# raspiledmeter.net
KiCad netlist of a schematic drawn in EAGLE
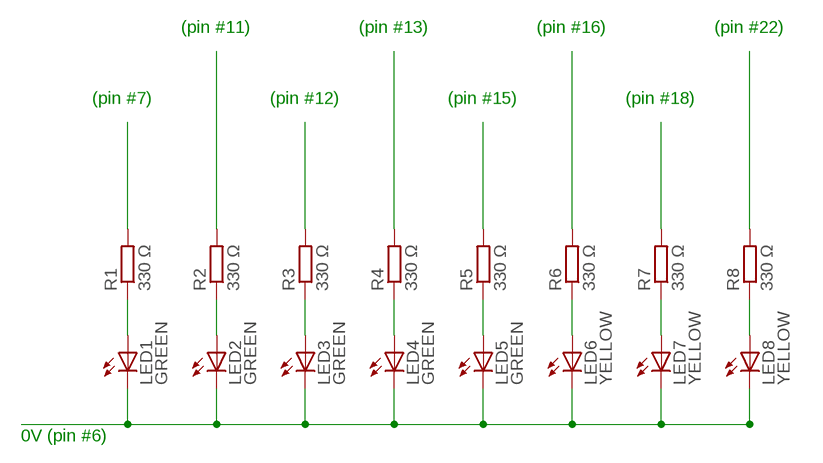
[diagram p0: schematic, sheet 1]

(export (version "E")
  (design (tool "Eeschema 10.0.6"))
  (components
    (comp (ref "LED1")
      (value "GREEN")
      (footprint "eagle-import:PLCC2")
      (libsource (lib "eagle-import") (part "_T679-?-1E1F1LG"))
    )
    (comp (ref "LED2")
      (value "GREEN")
      (footprint "eagle-import:PLCC2")
      (libsource (lib "eagle-import") (part "_T679-?-1E1F1LG"))
    )
    (comp (ref "LED3")
      (value "GREEN")
      (footprint "eagle-import:PLCC2")
      (libsource (lib "eagle-import") (part "_T679-?-1E1F1LG"))
    )
    (comp (ref "LED4")
      (value "GREEN")
      (footprint "eagle-import:PLCC2")
      (libsource (lib "eagle-import") (part "_T679-?-1E1F1LG"))
    )
    (comp (ref "LED5")
      (value "GREEN")
      (footprint "eagle-import:PLCC2")
      (libsource (lib "eagle-import") (part "_T679-?-1E1F1LG"))
    )
    (comp (ref "LED6")
      (value "YELLOW")
      (footprint "eagle-import:PLCC2")
      (libsource (lib "eagle-import") (part "_T679-?-1E1F1LG"))
    )
    (comp (ref "LED7")
      (value "YELLOW")
      (footprint "eagle-import:PLCC2")
      (libsource (lib "eagle-import") (part "_T679-?-1E1F1LG"))
    )
    (comp (ref "LED8")
      (value "YELLOW")
      (footprint "eagle-import:PLCC2")
      (libsource (lib "eagle-import") (part "_T679-?-1E1F1LG"))
    )
    (comp (ref "R1")
      (value "330 Ω")
      (footprint "eagle-import:0204V")
      (libsource (lib "eagle-import") (part "R-EU_0204/2V"))
    )
    (comp (ref "R2")
      (value "330 Ω")
      (footprint "eagle-import:0204V")
      (libsource (lib "eagle-import") (part "R-EU_0204/2V"))
    )
    (comp (ref "R3")
      (value "330 Ω")
      (footprint "eagle-import:0204V")
      (libsource (lib "eagle-import") (part "R-EU_0204/2V"))
    )
    (comp (ref "R4")
      (value "330 Ω")
      (footprint "eagle-import:0204V")
      (libsource (lib "eagle-import") (part "R-EU_0204/2V"))
    )
    (comp (ref "R5")
      (value "330 Ω")
      (footprint "eagle-import:0204V")
      (libsource (lib "eagle-import") (part "R-EU_0204/2V"))
    )
    (comp (ref "R6")
      (value "330 Ω")
      (footprint "eagle-import:0204V")
      (libsource (lib "eagle-import") (part "R-EU_0204/2V"))
    )
    (comp (ref "R7")
      (value "330 Ω")
      (footprint "eagle-import:0204V")
      (libsource (lib "eagle-import") (part "R-EU_0204/2V"))
    )
    (comp (ref "R8")
      (value "330 Ω")
      (footprint "eagle-import:0204V")
      (libsource (lib "eagle-import") (part "R-EU_0204/2V"))
    )
  )
  (nets
    (net (code "1") (name "Net-(LED1-PadA)") (class "Default")
      (node (ref "LED1") (pin "A") (pinfunction "A_A") (pintype "passive"))
      (node (ref "R1") (pin "1") (pinfunction "1_1") (pintype "passive"))
    )
    (net (code "2") (name "Net-(LED1-PadC)") (class "Default")
      (node (ref "LED1") (pin "C") (pinfunction "C_C") (pintype "passive"))
      (node (ref "LED2") (pin "C") (pinfunction "C_C") (pintype "passive"))
      (node (ref "LED3") (pin "C") (pinfunction "C_C") (pintype "passive"))
      (node (ref "LED4") (pin "C") (pinfunction "C_C") (pintype "passive"))
      (node (ref "LED5") (pin "C") (pinfunction "C_C") (pintype "passive"))
      (node (ref "LED6") (pin "C") (pinfunction "C_C") (pintype "passive"))
      (node (ref "LED7") (pin "C") (pinfunction "C_C") (pintype "passive"))
      (node (ref "LED8") (pin "C") (pinfunction "C_C") (pintype "passive"))
    )
    (net (code "3") (name "Net-(LED2-PadA)") (class "Default")
      (node (ref "LED2") (pin "A") (pinfunction "A_A") (pintype "passive"))
      (node (ref "R2") (pin "1") (pinfunction "1_1") (pintype "passive"))
    )
    (net (code "4") (name "Net-(LED3-PadA)") (class "Default")
      (node (ref "LED3") (pin "A") (pinfunction "A_A") (pintype "passive"))
      (node (ref "R3") (pin "1") (pinfunction "1_1") (pintype "passive"))
    )
    (net (code "5") (name "Net-(LED4-PadA)") (class "Default")
      (node (ref "LED4") (pin "A") (pinfunction "A_A") (pintype "passive"))
      (node (ref "R4") (pin "1") (pinfunction "1_1") (pintype "passive"))
    )
    (net (code "6") (name "Net-(LED5-PadA)") (class "Default")
      (node (ref "LED5") (pin "A") (pinfunction "A_A") (pintype "passive"))
      (node (ref "R5") (pin "1") (pinfunction "1_1") (pintype "passive"))
    )
    (net (code "7") (name "Net-(LED6-PadA)") (class "Default")
      (node (ref "LED6") (pin "A") (pinfunction "A_A") (pintype "passive"))
      (node (ref "R6") (pin "1") (pinfunction "1_1") (pintype "passive"))
    )
    (net (code "8") (name "Net-(LED7-PadA)") (class "Default")
      (node (ref "LED7") (pin "A") (pinfunction "A_A") (pintype "passive"))
      (node (ref "R7") (pin "1") (pinfunction "1_1") (pintype "passive"))
    )
    (net (code "9") (name "Net-(LED8-PadA)") (class "Default")
      (node (ref "LED8") (pin "A") (pinfunction "A_A") (pintype "passive"))
      (node (ref "R8") (pin "1") (pinfunction "1_1") (pintype "passive"))
    )
    (net (code "10") (name "unconnected-(R1-Pad2)") (class "Default")
      (node (ref "R1") (pin "2") (pinfunction "2_2") (pintype "passive"))
    )
    (net (code "11") (name "unconnected-(R2-Pad2)") (class "Default")
      (node (ref "R2") (pin "2") (pinfunction "2_2") (pintype "passive"))
    )
    (net (code "12") (name "unconnected-(R3-Pad2)") (class "Default")
      (node (ref "R3") (pin "2") (pinfunction "2_2") (pintype "passive"))
    )
    (net (code "13") (name "unconnected-(R4-Pad2)") (class "Default")
      (node (ref "R4") (pin "2") (pinfunction "2_2") (pintype "passive"))
    )
    (net (code "14") (name "unconnected-(R5-Pad2)") (class "Default")
      (node (ref "R5") (pin "2") (pinfunction "2_2") (pintype "passive"))
    )
    (net (code "15") (name "unconnected-(R6-Pad2)") (class "Default")
      (node (ref "R6") (pin "2") (pinfunction "2_2") (pintype "passive"))
    )
    (net (code "16") (name "unconnected-(R7-Pad2)") (class "Default")
      (node (ref "R7") (pin "2") (pinfunction "2_2") (pintype "passive"))
    )
    (net (code "17") (name "unconnected-(R8-Pad2)") (class "Default")
      (node (ref "R8") (pin "2") (pinfunction "2_2") (pintype "passive"))
    )
  )
)
